# HandeBatuProje.net
KiCad netlist of a schematic drawn in Altium Designer
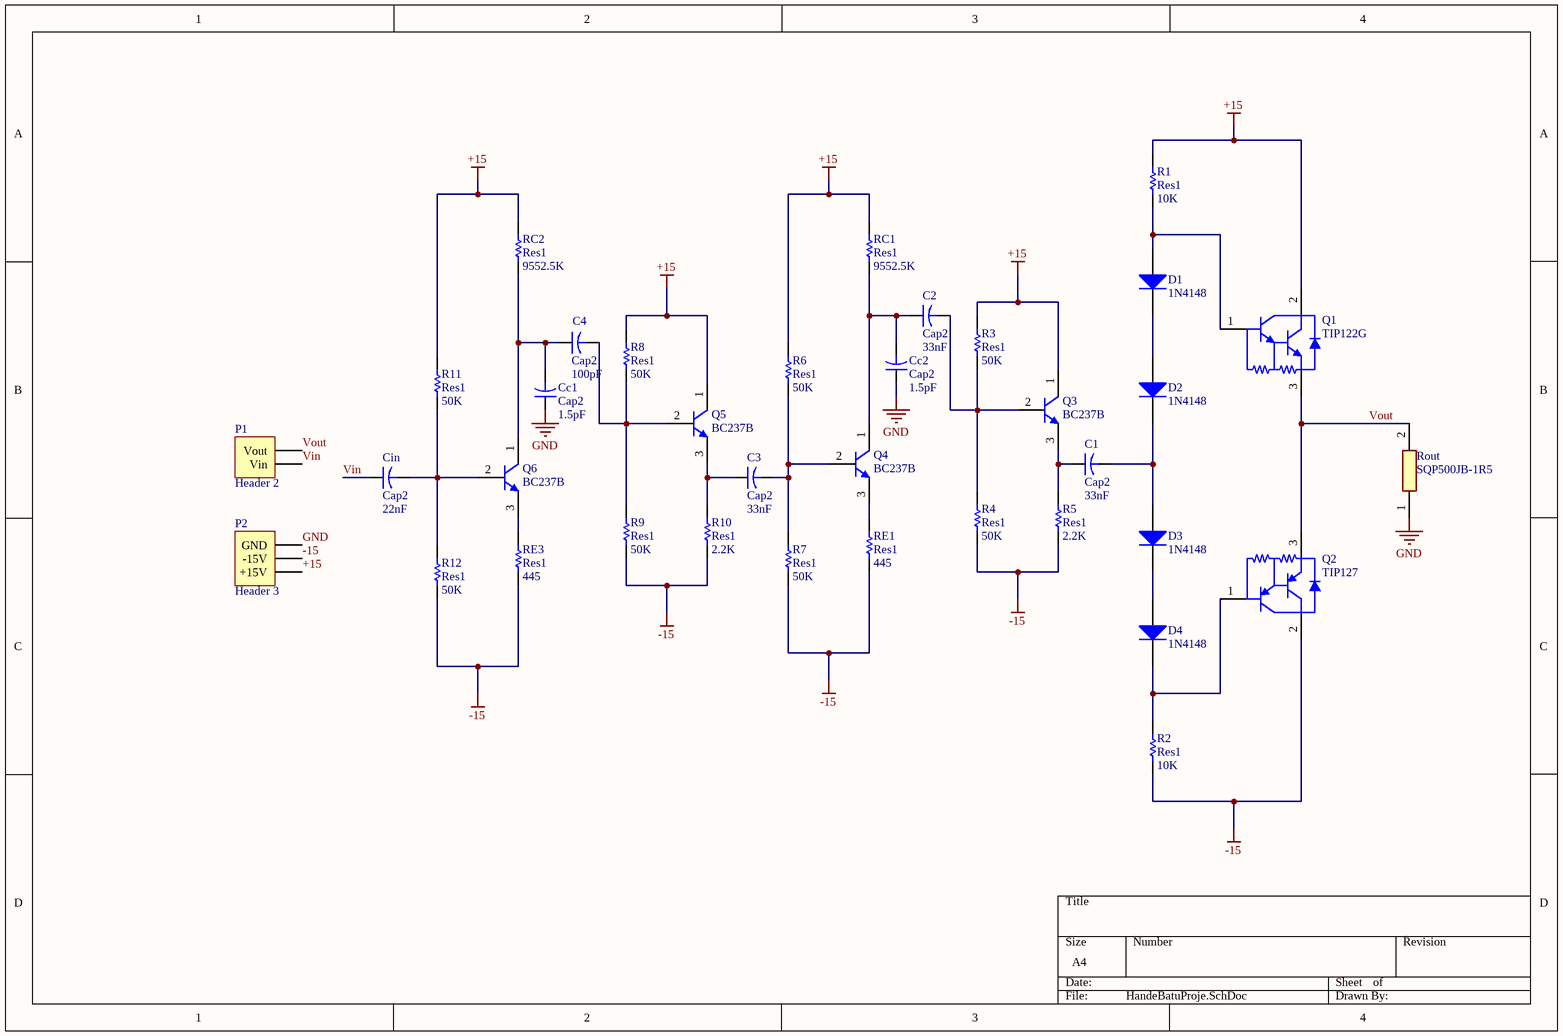
[diagram p0: HandeBatuProje.SchDoc]

(export (version "E")
  (design (tool "Eeschema 10.0.6"))
  (components
    (comp (ref "C1")
      (value "Cap2")
      (footprint "CAPR5-4X5")
      (description "Capacitor")
      (fields (field (name "ALTIUM_VALUE") "33nF") (field (name "PUBLISHER") "Altium Limited"))
      (libsource (lib "Miscellaneous Devices") (part "Cap2"))
    )
    (comp (ref "C2")
      (value "Cap2")
      (footprint "CAPR5-4X5")
      (description "Capacitor")
      (fields (field (name "ALTIUM_VALUE") "33nF") (field (name "PUBLISHER") "Altium Limited"))
      (libsource (lib "Miscellaneous Devices") (part "Cap2"))
    )
    (comp (ref "C3")
      (value "Cap2")
      (footprint "CAPR5-4X5")
      (description "Capacitor")
      (fields (field (name "ALTIUM_VALUE") "33nF") (field (name "PUBLISHER") "Altium Limited"))
      (libsource (lib "Miscellaneous Devices") (part "Cap2"))
    )
    (comp (ref "C4")
      (value "Cap2")
      (footprint "CAPR5-4X5")
      (description "Capacitor")
      (fields (field (name "ALTIUM_VALUE") "100pF") (field (name "PUBLISHER") "Altium Limited"))
      (libsource (lib "Miscellaneous Devices") (part "Cap2"))
    )
    (comp (ref "Cc1")
      (value "Cap2")
      (footprint "CAPR5-4X5")
      (description "Capacitor")
      (fields (field (name "ALTIUM_VALUE") "1.5pF") (field (name "PUBLISHER") "Altium Limited"))
      (libsource (lib "Miscellaneous Devices") (part "Cap2"))
    )
    (comp (ref "Cc2")
      (value "Cap2")
      (footprint "CAPR5-4X5")
      (description "Capacitor")
      (fields (field (name "ALTIUM_VALUE") "1.5pF") (field (name "PUBLISHER") "Altium Limited"))
      (libsource (lib "Miscellaneous Devices") (part "Cap2"))
    )
    (comp (ref "Cin")
      (value "Cap2")
      (footprint "CAPR5-4X5")
      (description "Capacitor")
      (fields (field (name "ALTIUM_VALUE") "22nF") (field (name "PUBLISHER") "Altium Limited"))
      (libsource (lib "Miscellaneous Devices") (part "Cap2"))
    )
    (comp (ref "D1")
      (value "1N4148")
      (footprint "NXP-SOD27-2_V")
      (description "High-speed Diode, 100 V, 450 mA, 2-Pin SOD27, RoHS")
      (fields (field (name "MANUFACTURER") "NXP Semiconductors"))
      (libsource (lib "Altium Content Vault") (part "NXP-A1K2-2"))
    )
    (comp (ref "D2")
      (value "1N4148")
      (footprint "NXP-SOD27-2_V")
      (description "High-speed Diode, 100 V, 450 mA, 2-Pin SOD27, RoHS")
      (fields (field (name "MANUFACTURER") "NXP Semiconductors"))
      (libsource (lib "Altium Content Vault") (part "NXP-A1K2-2"))
    )
    (comp (ref "D3")
      (value "1N4148")
      (footprint "NXP-SOD27-2_V")
      (description "High-speed Diode, 100 V, 450 mA, 2-Pin SOD27, RoHS")
      (fields (field (name "MANUFACTURER") "NXP Semiconductors"))
      (libsource (lib "Altium Content Vault") (part "NXP-A1K2-2"))
    )
    (comp (ref "D4")
      (value "1N4148")
      (footprint "NXP-SOD27-2_V")
      (description "High-speed Diode, 100 V, 450 mA, 2-Pin SOD27, RoHS")
      (fields (field (name "MANUFACTURER") "NXP Semiconductors"))
      (libsource (lib "Altium Content Vault") (part "NXP-A1K2-2"))
    )
    (comp (ref "P1")
      (value "Header 2")
      (footprint "HDR1X2")
      (description "Header, 2-Pin")
      (fields (field (name "PUBLISHER") "Altium Limited"))
      (libsource (lib "Miscellaneous Connectors") (part "Header 2"))
    )
    (comp (ref "P2")
      (value "Header 3")
      (footprint "HDR1X3")
      (description "Header, 3-Pin")
      (fields (field (name "PUBLISHER") "Altium Limited"))
      (libsource (lib "Miscellaneous Connectors") (part "Header 3"))
    )
    (comp (ref "Q1")
      (value "TIP122G")
      (footprint "ONSC-TO-220-3-221A-09")
      (description "Plastic Medium-Power, Complementary Silicon Transistor, 3-Pin TO-220, Pb-Free, Tube")
      (fields (field (name "MANUFACTURER") "On Semiconductor"))
      (libsource (lib "Altium Content Vault") (part "ONSC-DT-NPN-B1C2E3-3_A"))
    )
    (comp (ref "Q2")
      (value "TIP127")
      (footprint "ONSC-TO-220-3-221A-09")
      (description "Plastic Medium-Power, Complementary Silicon Transistor, 3-Pin TO-220, Tube")
      (fields (field (name "MANUFACTURER") "On Semiconductor"))
      (libsource (lib "Altium Content Vault") (part "ONSC-DT-PNP-B1C2E3-3"))
    )
    (comp (ref "Q3")
      (value "BC237B")
      (footprint "ONSC-TO-92-3-29-11")
      (description "Amplifier Transistor, NPN Silicon, 3-Pin TO-92, Bulk Box")
      (fields (field (name "MANUFACTURER") "On Semiconductor"))
      (libsource (lib "Altium Content Vault") (part "ONSC-NPN-C1B2E3-3"))
    )
    (comp (ref "Q4")
      (value "BC237B")
      (footprint "ONSC-TO-92-3-29-11")
      (description "Amplifier Transistor, NPN Silicon, 3-Pin TO-92, Bulk Box")
      (fields (field (name "MANUFACTURER") "On Semiconductor"))
      (libsource (lib "Altium Content Vault") (part "ONSC-NPN-C1B2E3-3"))
    )
    (comp (ref "Q5")
      (value "BC237B")
      (footprint "ONSC-TO-92-3-29-11")
      (description "Amplifier Transistor, NPN Silicon, 3-Pin TO-92, Bulk Box")
      (fields (field (name "MANUFACTURER") "On Semiconductor"))
      (libsource (lib "Altium Content Vault") (part "ONSC-NPN-C1B2E3-3"))
    )
    (comp (ref "Q6")
      (value "BC237B")
      (footprint "ONSC-TO-92-3-29-11")
      (description "Amplifier Transistor, NPN Silicon, 3-Pin TO-92, Bulk Box")
      (fields (field (name "MANUFACTURER") "On Semiconductor"))
      (libsource (lib "Altium Content Vault") (part "ONSC-NPN-C1B2E3-3"))
    )
    (comp (ref "R1")
      (value "Res1")
      (footprint "AXIAL-0.3")
      (description "Resistor")
      (fields (field (name "ALTIUM_VALUE") "10K") (field (name "PUBLISHER") "Altium Limited"))
      (libsource (lib "Miscellaneous Devices") (part "Res1"))
    )
    (comp (ref "R2")
      (value "Res1")
      (footprint "AXIAL-0.3")
      (description "Resistor")
      (fields (field (name "ALTIUM_VALUE") "10K") (field (name "PUBLISHER") "Altium Limited"))
      (libsource (lib "Miscellaneous Devices") (part "Res1"))
    )
    (comp (ref "R3")
      (value "Res1")
      (footprint "AXIAL-0.3")
      (description "Resistor")
      (fields (field (name "ALTIUM_VALUE") "50K") (field (name "PUBLISHER") "Altium Limited"))
      (libsource (lib "Miscellaneous Devices") (part "Res1"))
    )
    (comp (ref "R4")
      (value "Res1")
      (footprint "AXIAL-0.3")
      (description "Resistor")
      (fields (field (name "ALTIUM_VALUE") "50K") (field (name "PUBLISHER") "Altium Limited"))
      (libsource (lib "Miscellaneous Devices") (part "Res1"))
    )
    (comp (ref "R5")
      (value "Res1")
      (footprint "AXIAL-0.3")
      (description "Resistor")
      (fields (field (name "ALTIUM_VALUE") "2.2K") (field (name "PUBLISHER") "Altium Limited"))
      (libsource (lib "Miscellaneous Devices") (part "Res1"))
    )
    (comp (ref "R6")
      (value "Res1")
      (footprint "AXIAL-0.3")
      (description "Resistor")
      (fields (field (name "ALTIUM_VALUE") "50K") (field (name "PUBLISHER") "Altium Limited"))
      (libsource (lib "Miscellaneous Devices") (part "Res1"))
    )
    (comp (ref "R7")
      (value "Res1")
      (footprint "AXIAL-0.3")
      (description "Resistor")
      (fields (field (name "ALTIUM_VALUE") "50K") (field (name "PUBLISHER") "Altium Limited"))
      (libsource (lib "Miscellaneous Devices") (part "Res1"))
    )
    (comp (ref "R8")
      (value "Res1")
      (footprint "AXIAL-0.3")
      (description "Resistor")
      (fields (field (name "ALTIUM_VALUE") "50K") (field (name "PUBLISHER") "Altium Limited"))
      (libsource (lib "Miscellaneous Devices") (part "Res1"))
    )
    (comp (ref "R9")
      (value "Res1")
      (footprint "AXIAL-0.3")
      (description "Resistor")
      (fields (field (name "ALTIUM_VALUE") "50K") (field (name "PUBLISHER") "Altium Limited"))
      (libsource (lib "Miscellaneous Devices") (part "Res1"))
    )
    (comp (ref "R10")
      (value "Res1")
      (footprint "AXIAL-0.3")
      (description "Resistor")
      (fields (field (name "ALTIUM_VALUE") "2.2K") (field (name "PUBLISHER") "Altium Limited"))
      (libsource (lib "Miscellaneous Devices") (part "Res1"))
    )
    (comp (ref "R11")
      (value "Res1")
      (footprint "AXIAL-0.3")
      (description "Resistor")
      (fields (field (name "ALTIUM_VALUE") "50K") (field (name "PUBLISHER") "Altium Limited"))
      (libsource (lib "Miscellaneous Devices") (part "Res1"))
    )
    (comp (ref "R12")
      (value "Res1")
      (footprint "AXIAL-0.3")
      (description "Resistor")
      (fields (field (name "ALTIUM_VALUE") "50K") (field (name "PUBLISHER") "Altium Limited"))
      (libsource (lib "Miscellaneous Devices") (part "Res1"))
    )
    (comp (ref "RC1")
      (value "Res1")
      (footprint "AXIAL-0.3")
      (description "Resistor")
      (fields (field (name "ALTIUM_VALUE") "9552.5K") (field (name "PUBLISHER") "Altium Limited"))
      (libsource (lib "Miscellaneous Devices") (part "Res1"))
    )
    (comp (ref "RC2")
      (value "Res1")
      (footprint "AXIAL-0.3")
      (description "Resistor")
      (fields (field (name "ALTIUM_VALUE") "9552.5K") (field (name "PUBLISHER") "Altium Limited"))
      (libsource (lib "Miscellaneous Devices") (part "Res1"))
    )
    (comp (ref "RE1")
      (value "Res1")
      (footprint "AXIAL-0.3")
      (description "Resistor")
      (fields (field (name "ALTIUM_VALUE") "445") (field (name "PUBLISHER") "Altium Limited"))
      (libsource (lib "Miscellaneous Devices") (part "Res1"))
    )
    (comp (ref "RE3")
      (value "Res1")
      (footprint "AXIAL-0.3")
      (description "Resistor")
      (fields (field (name "ALTIUM_VALUE") "445") (field (name "PUBLISHER") "Altium Limited"))
      (libsource (lib "Miscellaneous Devices") (part "Res1"))
    )
    (comp (ref "Rout")
      (value "SQP500JB-1R5")
      (footprint "SamacSys:RESAD6000W85L2200D950")
      (description "Resistor")
      (fields (field (name "MOUSER PART NUMBER") "603-SQP500JB-1R5"))
      (libsource (lib "*") (part "SQP500JB-1R5"))
    )
  )
  (nets
    (net (code "1") (name "+15") (class "Default")
      (node (ref "P2") (pin "1") (pinfunction "+15V_1") (pintype "passive"))
      (node (ref "Q1") (pin "2") (pinfunction "C_2") (pintype "passive"))
      (node (ref "Q3") (pin "1") (pinfunction "C_1") (pintype "passive"))
      (node (ref "Q5") (pin "1") (pinfunction "C_1") (pintype "passive"))
      (node (ref "R1") (pin "1") (pinfunction "1_1") (pintype "passive"))
      (node (ref "R11") (pin "1") (pinfunction "1_1") (pintype "passive"))
      (node (ref "R3") (pin "1") (pinfunction "1_1") (pintype "passive"))
      (node (ref "R6") (pin "1") (pinfunction "1_1") (pintype "passive"))
      (node (ref "R8") (pin "1") (pinfunction "1_1") (pintype "passive"))
      (node (ref "RC1") (pin "1") (pinfunction "1_1") (pintype "passive"))
      (node (ref "RC2") (pin "1") (pinfunction "1_1") (pintype "passive"))
    )
    (net (code "2") (name "-15") (class "Default")
      (node (ref "P2") (pin "2") (pinfunction "-15V_2") (pintype "passive"))
      (node (ref "Q2") (pin "2") (pinfunction "C_2") (pintype "passive"))
      (node (ref "R10") (pin "2") (pinfunction "2_2") (pintype "passive"))
      (node (ref "R12") (pin "2") (pinfunction "2_2") (pintype "passive"))
      (node (ref "R2") (pin "2") (pinfunction "2_2") (pintype "passive"))
      (node (ref "R4") (pin "2") (pinfunction "2_2") (pintype "passive"))
      (node (ref "R5") (pin "2") (pinfunction "2_2") (pintype "passive"))
      (node (ref "R7") (pin "2") (pinfunction "2_2") (pintype "passive"))
      (node (ref "R9") (pin "2") (pinfunction "2_2") (pintype "passive"))
      (node (ref "RE1") (pin "2") (pinfunction "2_2") (pintype "passive"))
      (node (ref "RE3") (pin "2") (pinfunction "2_2") (pintype "passive"))
    )
    (net (code "3") (name "/Vin") (class "Default")
      (node (ref "Cin") (pin "1") (pinfunction "1_1") (pintype "passive"))
      (node (ref "P1") (pin "1") (pinfunction "Vin_1") (pintype "passive"))
    )
    (net (code "4") (name "/Vout") (class "Default")
      (node (ref "P1") (pin "2") (pinfunction "Vout_2") (pintype "passive"))
      (node (ref "Q1") (pin "3") (pinfunction "E_3") (pintype "passive"))
      (node (ref "Q2") (pin "3") (pinfunction "E_3") (pintype "passive"))
      (node (ref "Rout") (pin "2") (pinfunction "2_2") (pintype "passive"))
    )
    (net (code "5") (name "GND") (class "Default")
      (node (ref "Cc1") (pin "1") (pinfunction "1_1") (pintype "passive"))
      (node (ref "Cc2") (pin "1") (pinfunction "1_1") (pintype "passive"))
      (node (ref "P2") (pin "3") (pinfunction "GND_3") (pintype "passive"))
      (node (ref "Rout") (pin "1") (pinfunction "1_1") (pintype "passive"))
    )
    (net (code "6") (name "Net-(D1-A)") (class "Default")
      (node (ref "D1") (pin "1") (pinfunction "A_1") (pintype "passive"))
      (node (ref "Q1") (pin "1") (pinfunction "B_1") (pintype "passive"))
      (node (ref "R1") (pin "2") (pinfunction "2_2") (pintype "passive"))
    )
    (net (code "7") (name "Net-(D1-K)") (class "Default")
      (node (ref "D1") (pin "2") (pinfunction "K_2") (pintype "passive"))
      (node (ref "D2") (pin "1") (pinfunction "A_1") (pintype "passive"))
    )
    (net (code "8") (name "Net-(D2-K)") (class "Default")
      (node (ref "C1") (pin "2") (pinfunction "2_2") (pintype "passive"))
      (node (ref "D2") (pin "2") (pinfunction "K_2") (pintype "passive"))
      (node (ref "D3") (pin "1") (pinfunction "A_1") (pintype "passive"))
    )
    (net (code "9") (name "Net-(D3-K)") (class "Default")
      (node (ref "D3") (pin "2") (pinfunction "K_2") (pintype "passive"))
      (node (ref "D4") (pin "1") (pinfunction "A_1") (pintype "passive"))
    )
    (net (code "10") (name "Net-(D4-K)") (class "Default")
      (node (ref "D4") (pin "2") (pinfunction "K_2") (pintype "passive"))
      (node (ref "Q2") (pin "1") (pinfunction "B_1") (pintype "passive"))
      (node (ref "R2") (pin "1") (pinfunction "1_1") (pintype "passive"))
    )
    (net (code "11") (name "Net-(Q3-B)") (class "Default")
      (node (ref "C2") (pin "2") (pinfunction "2_2") (pintype "passive"))
      (node (ref "Q3") (pin "2") (pinfunction "B_2") (pintype "passive"))
      (node (ref "R3") (pin "2") (pinfunction "2_2") (pintype "passive"))
      (node (ref "R4") (pin "1") (pinfunction "1_1") (pintype "passive"))
    )
    (net (code "12") (name "Net-(Q3-E)") (class "Default")
      (node (ref "C1") (pin "1") (pinfunction "1_1") (pintype "passive"))
      (node (ref "Q3") (pin "3") (pinfunction "E_3") (pintype "passive"))
      (node (ref "R5") (pin "1") (pinfunction "1_1") (pintype "passive"))
    )
    (net (code "13") (name "Net-(Q4-B)") (class "Default")
      (node (ref "C3") (pin "2") (pinfunction "2_2") (pintype "passive"))
      (node (ref "Q4") (pin "2") (pinfunction "B_2") (pintype "passive"))
      (node (ref "R6") (pin "2") (pinfunction "2_2") (pintype "passive"))
      (node (ref "R7") (pin "1") (pinfunction "1_1") (pintype "passive"))
    )
    (net (code "14") (name "Net-(Q4-C)") (class "Default")
      (node (ref "C2") (pin "1") (pinfunction "1_1") (pintype "passive"))
      (node (ref "Cc2") (pin "2") (pinfunction "2_2") (pintype "passive"))
      (node (ref "Q4") (pin "1") (pinfunction "C_1") (pintype "passive"))
      (node (ref "RC1") (pin "2") (pinfunction "2_2") (pintype "passive"))
    )
    (net (code "15") (name "Net-(Q4-E)") (class "Default")
      (node (ref "Q4") (pin "3") (pinfunction "E_3") (pintype "passive"))
      (node (ref "RE1") (pin "1") (pinfunction "1_1") (pintype "passive"))
    )
    (net (code "16") (name "Net-(Q5-B)") (class "Default")
      (node (ref "C4") (pin "2") (pinfunction "2_2") (pintype "passive"))
      (node (ref "Q5") (pin "2") (pinfunction "B_2") (pintype "passive"))
      (node (ref "R8") (pin "2") (pinfunction "2_2") (pintype "passive"))
      (node (ref "R9") (pin "1") (pinfunction "1_1") (pintype "passive"))
    )
    (net (code "17") (name "Net-(Q5-E)") (class "Default")
      (node (ref "C3") (pin "1") (pinfunction "1_1") (pintype "passive"))
      (node (ref "Q5") (pin "3") (pinfunction "E_3") (pintype "passive"))
      (node (ref "R10") (pin "1") (pinfunction "1_1") (pintype "passive"))
    )
    (net (code "18") (name "Net-(Q6-B)") (class "Default")
      (node (ref "Cin") (pin "2") (pinfunction "2_2") (pintype "passive"))
      (node (ref "Q6") (pin "2") (pinfunction "B_2") (pintype "passive"))
      (node (ref "R11") (pin "2") (pinfunction "2_2") (pintype "passive"))
      (node (ref "R12") (pin "1") (pinfunction "1_1") (pintype "passive"))
    )
    (net (code "19") (name "Net-(Q6-C)") (class "Default")
      (node (ref "C4") (pin "1") (pinfunction "1_1") (pintype "passive"))
      (node (ref "Cc1") (pin "2") (pinfunction "2_2") (pintype "passive"))
      (node (ref "Q6") (pin "1") (pinfunction "C_1") (pintype "passive"))
      (node (ref "RC2") (pin "2") (pinfunction "2_2") (pintype "passive"))
    )
    (net (code "20") (name "Net-(Q6-E)") (class "Default")
      (node (ref "Q6") (pin "3") (pinfunction "E_3") (pintype "passive"))
      (node (ref "RE3") (pin "1") (pinfunction "1_1") (pintype "passive"))
    )
  )
)
